# CPU_IO.net
KiCad netlist of a schematic drawn in Altium Designer
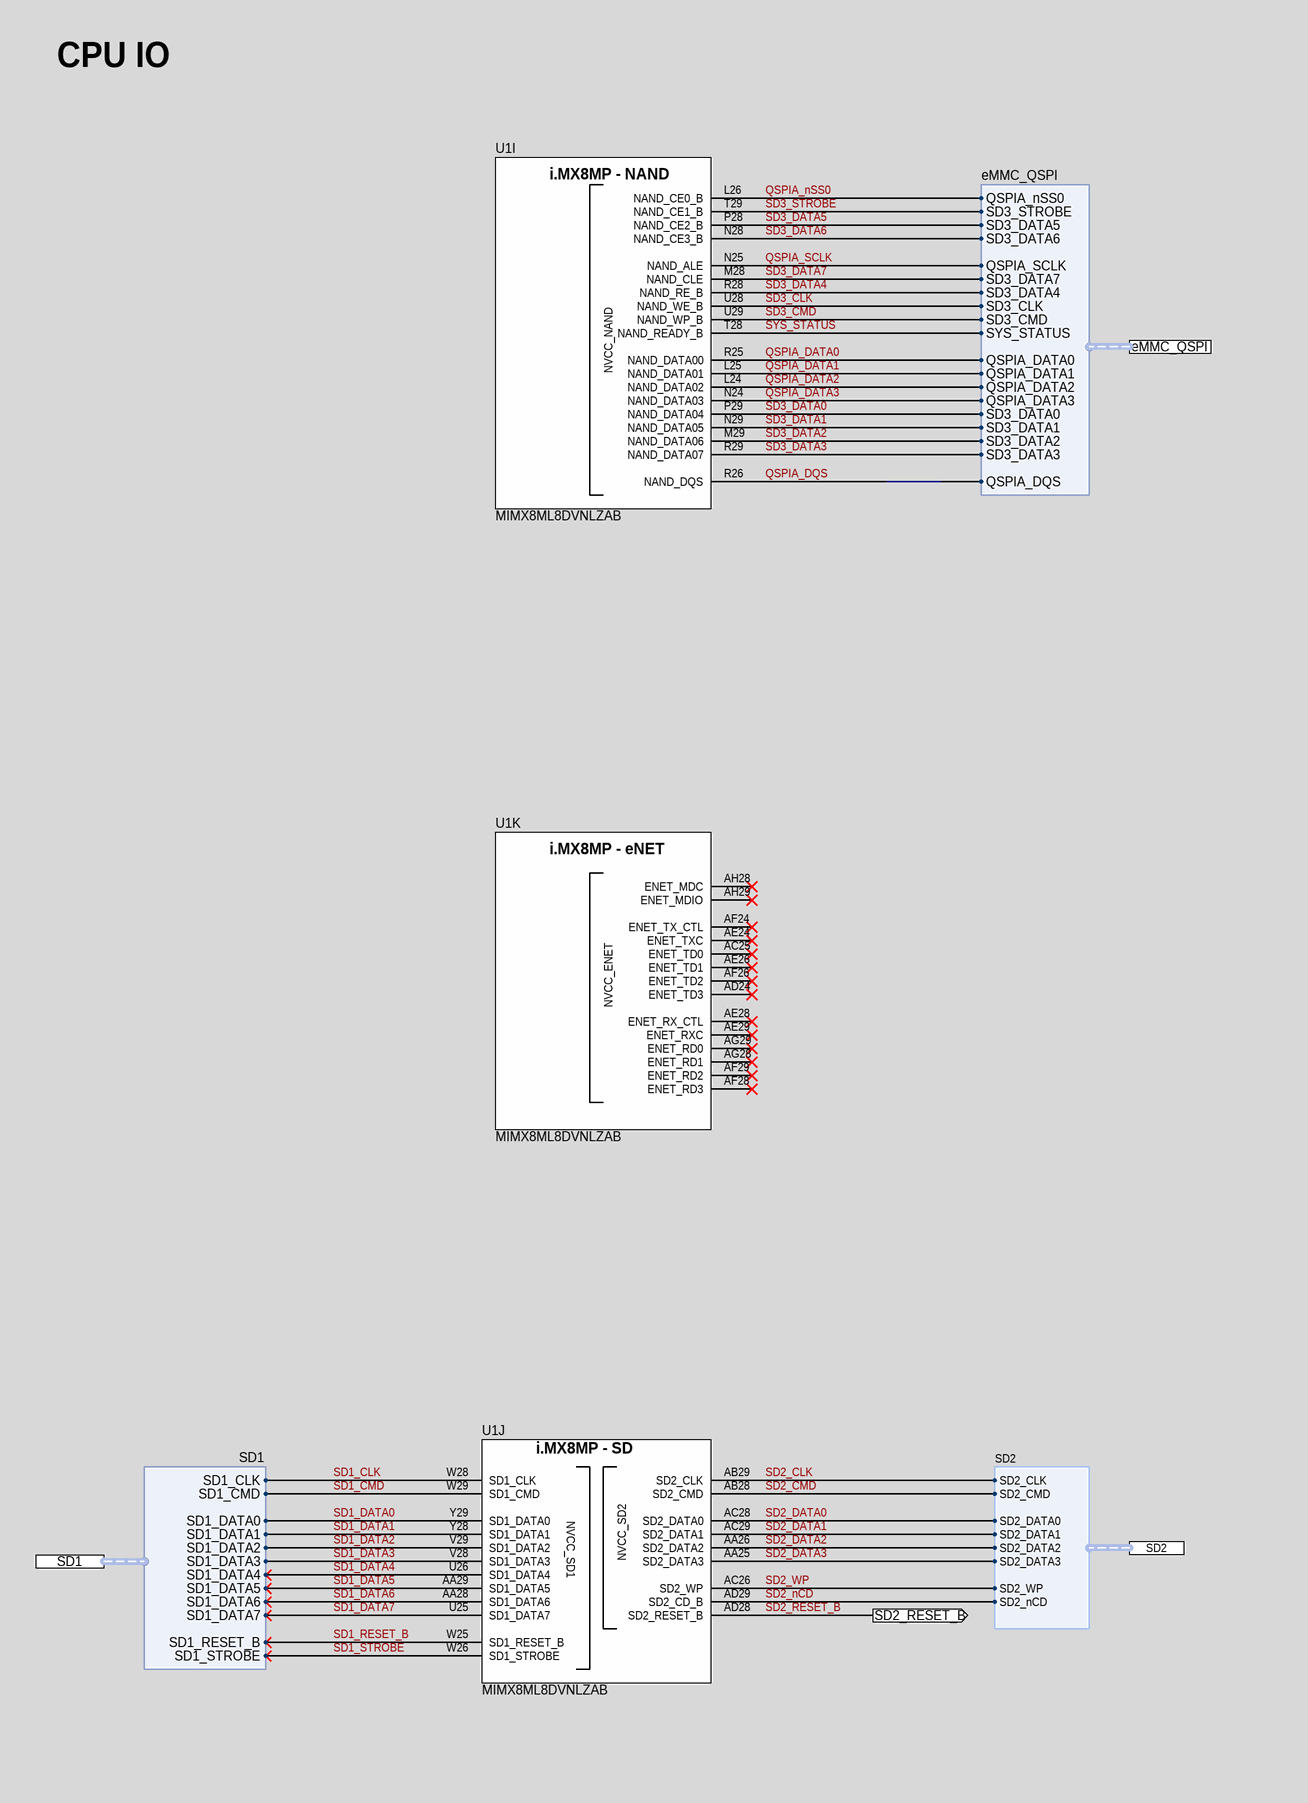
[diagram p0: CPU IO.SchDoc, left]
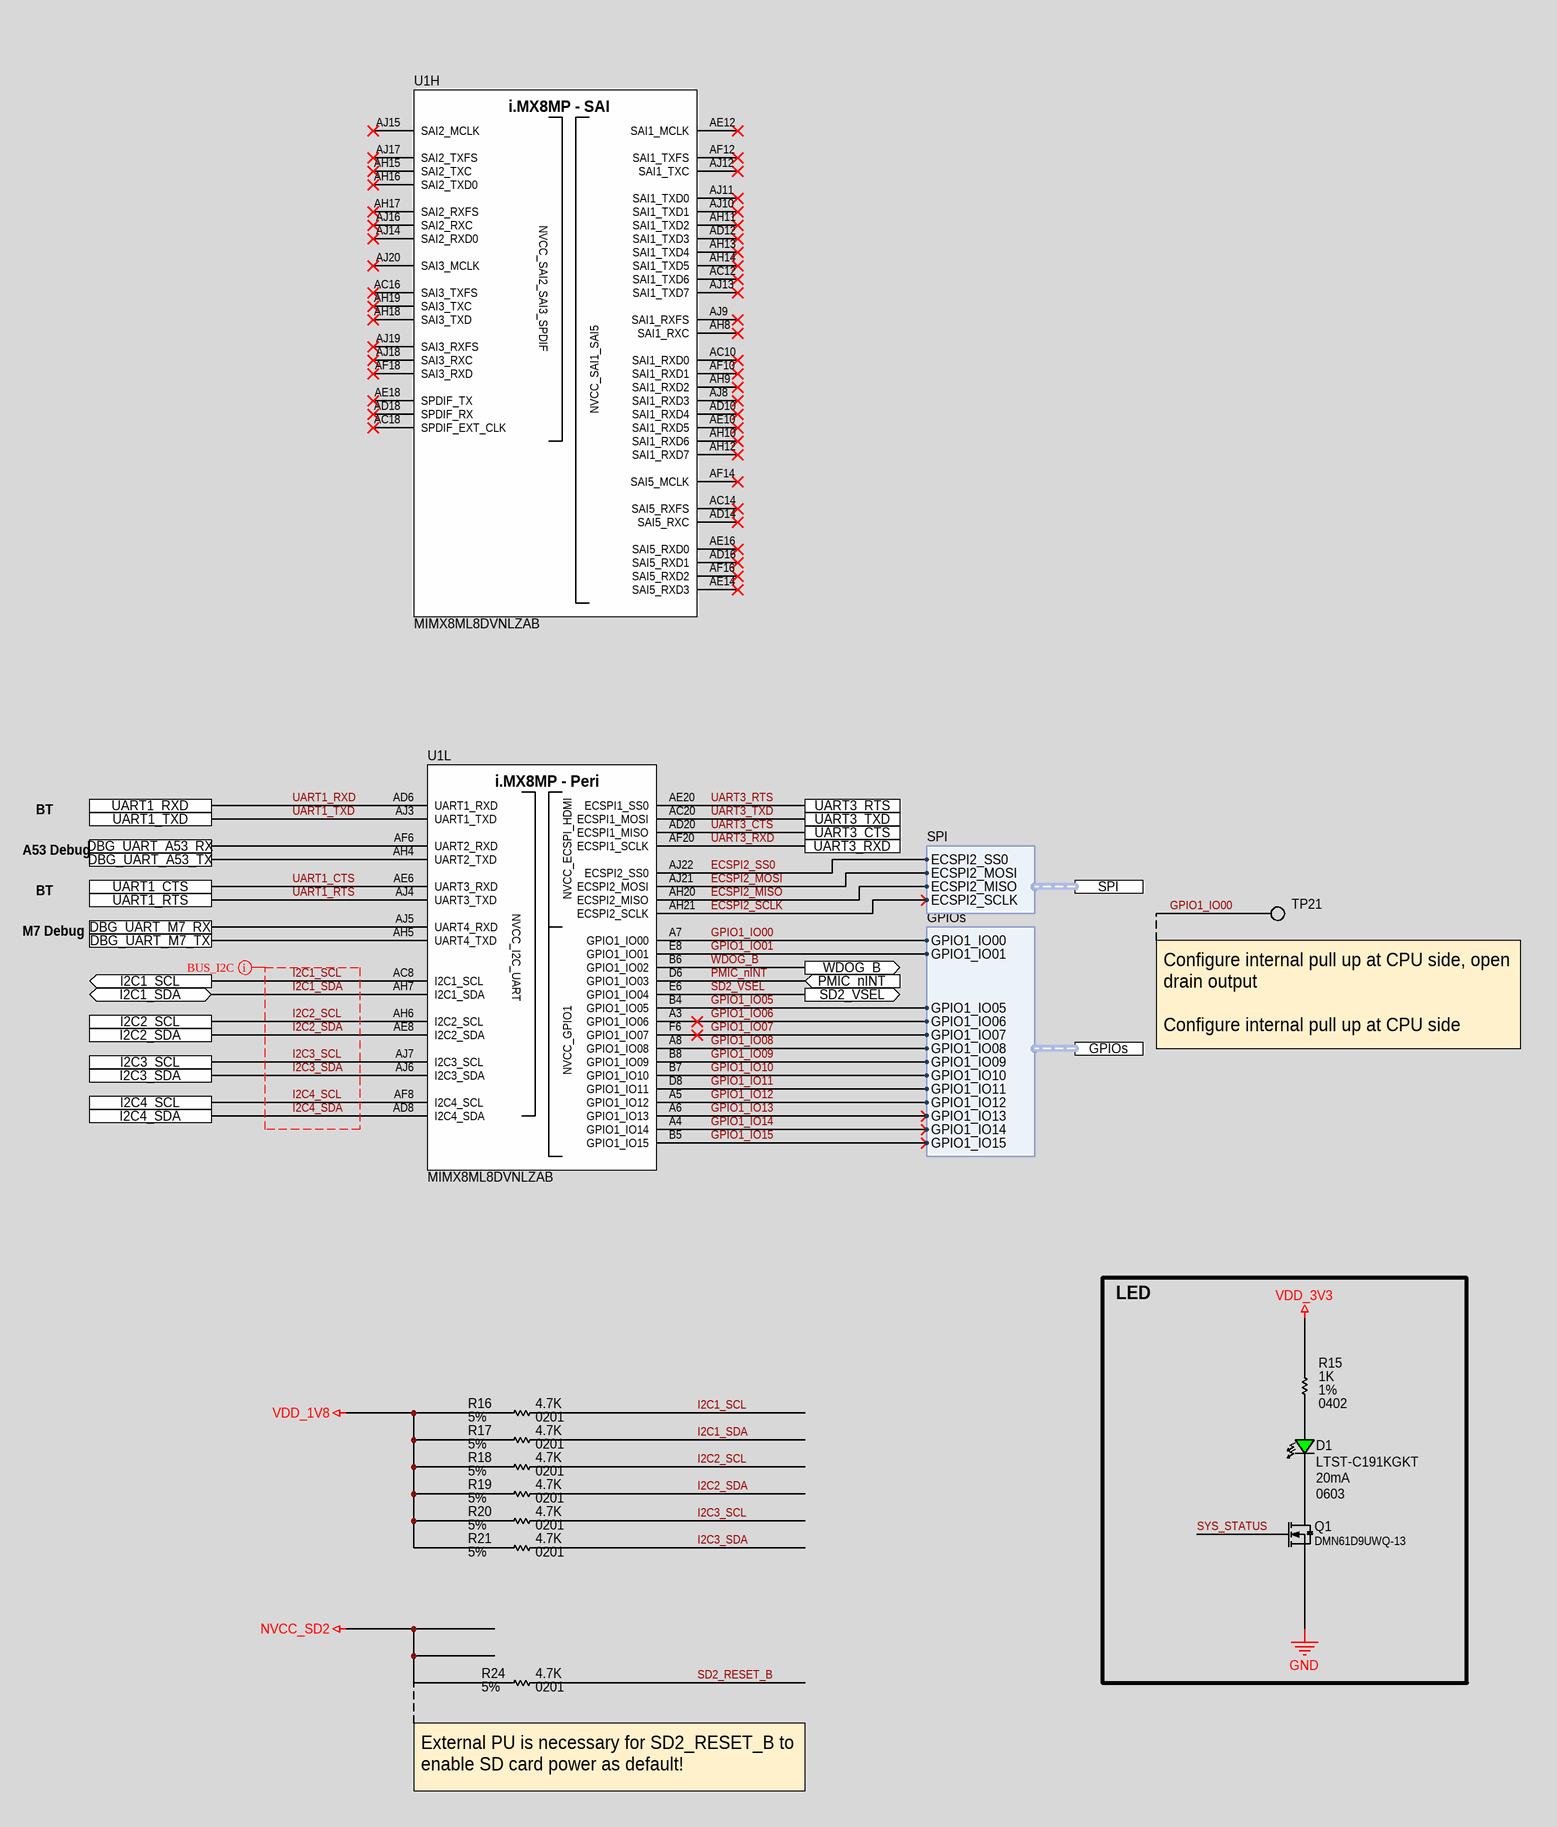
[diagram p1: CPU IO.SchDoc, right]

(export (version "E")
  (design (tool "Eeschema 10.0.6"))
  (components
    (comp (ref "D1")
      (value "LTST-C191KGKT")
      (footprint "LED_0603-GREEN")
      (description "LTST-C191KGKT Lite-On LED, green, 18-71mcd, 130, 1.9V-2.4V SMD, 0603 1.6x0.8x0.55mm RoHS")
      (fields
        (field (name "MANUFACTURER") "Vishay Lite-On")
        (field (name "TEST CURRENT") "20mA")
        (field (name "CASE/PACKAGE") "0603")
      )
      (libsource (lib "Electronic Devices_LIB") (part "LED_DIO_GREEN_20mA_0603"))
    )
    (comp (ref "Q1")
      (value "DMN61D9UWQ-13")
      (footprint "SOT-323")
      (description "N-Channel Enhancement Mode MOSFET 60V 340mA 3-Pin SOT-323 T/R")
      (fields (field (name "MANUFACTURER") "Diodes"))
      (libsource (lib "Electronic Devices_LIB") (part "TRANS_FET_CHA_N_60V_340mA"))
    )
    (comp (ref "R15")
      (value "ERJ-2RKF1001X")
      (footprint "RES_0402_RESC1005X04N")
      (description "RES SMD 1K OHM 1% 1/10W 0402")
      (fields
        (field (name "MANUFACTURER") "Panasonic")
        (field (name "RESISTANCE") "1K")
        (field (name "TOLERANCE") "1%")
        (field (name "CASE/PACKAGE") "0402")
      )
      (libsource (lib "Electronic Devices_LIB") (part "RES_1K_1%_100mW_0402"))
    )
    (comp (ref "R16")
      (value "RK73B1HTTC472J")
      (footprint "RES_0201_RESC0603X02N")
      (description "Res Thick Film 0201 4.7K Ohm 5% 0.05W(1/20W) ±200ppm/C Pad SMD Automotive T/R")
      (fields
        (field (name "MANUFACTURER") "KOA Speer")
        (field (name "TOLERANCE") "5%")
        (field (name "RESISTANCE") "4.7K")
        (field (name "CASE/PACKAGE") "0201")
      )
      (libsource (lib "Electronic Devices_LIB") (part "RES_4.7K_5%_50mW_0201"))
    )
    (comp (ref "R17")
      (value "RK73B1HTTC472J")
      (footprint "RES_0201_RESC0603X02N")
      (description "Res Thick Film 0201 4.7K Ohm 5% 0.05W(1/20W) ±200ppm/C Pad SMD Automotive T/R")
      (fields
        (field (name "MANUFACTURER") "KOA Speer")
        (field (name "TOLERANCE") "5%")
        (field (name "RESISTANCE") "4.7K")
        (field (name "CASE/PACKAGE") "0201")
      )
      (libsource (lib "Electronic Devices_LIB") (part "RES_4.7K_5%_50mW_0201"))
    )
    (comp (ref "R18")
      (value "RK73B1HTTC472J")
      (footprint "RES_0201_RESC0603X02N")
      (description "Res Thick Film 0201 4.7K Ohm 5% 0.05W(1/20W) ±200ppm/C Pad SMD Automotive T/R")
      (fields
        (field (name "MANUFACTURER") "KOA Speer")
        (field (name "TOLERANCE") "5%")
        (field (name "RESISTANCE") "4.7K")
        (field (name "CASE/PACKAGE") "0201")
      )
      (libsource (lib "Electronic Devices_LIB") (part "RES_4.7K_5%_50mW_0201"))
    )
    (comp (ref "R19")
      (value "RK73B1HTTC472J")
      (footprint "RES_0201_RESC0603X02N")
      (description "Res Thick Film 0201 4.7K Ohm 5% 0.05W(1/20W) ±200ppm/C Pad SMD Automotive T/R")
      (fields
        (field (name "MANUFACTURER") "KOA Speer")
        (field (name "TOLERANCE") "5%")
        (field (name "RESISTANCE") "4.7K")
        (field (name "CASE/PACKAGE") "0201")
      )
      (libsource (lib "Electronic Devices_LIB") (part "RES_4.7K_5%_50mW_0201"))
    )
    (comp (ref "R20")
      (value "RK73B1HTTC472J")
      (footprint "RES_0201_RESC0603X02N")
      (description "Res Thick Film 0201 4.7K Ohm 5% 0.05W(1/20W) ±200ppm/C Pad SMD Automotive T/R")
      (fields
        (field (name "MANUFACTURER") "KOA Speer")
        (field (name "TOLERANCE") "5%")
        (field (name "RESISTANCE") "4.7K")
        (field (name "CASE/PACKAGE") "0201")
      )
      (libsource (lib "Electronic Devices_LIB") (part "RES_4.7K_5%_50mW_0201"))
    )
    (comp (ref "R21")
      (value "RK73B1HTTC472J")
      (footprint "RES_0201_RESC0603X02N")
      (description "Res Thick Film 0201 4.7K Ohm 5% 0.05W(1/20W) ±200ppm/C Pad SMD Automotive T/R")
      (fields
        (field (name "MANUFACTURER") "KOA Speer")
        (field (name "TOLERANCE") "5%")
        (field (name "RESISTANCE") "4.7K")
        (field (name "CASE/PACKAGE") "0201")
      )
      (libsource (lib "Electronic Devices_LIB") (part "RES_4.7K_5%_50mW_0201"))
    )
    (comp (ref "R24")
      (value "RK73B1HTTC472J")
      (footprint "RES_0201_RESC0603X02N")
      (description "Res Thick Film 0201 4.7K Ohm 5% 0.05W(1/20W) ±200ppm/C Pad SMD Automotive T/R")
      (fields
        (field (name "MANUFACTURER") "KOA Speer")
        (field (name "TOLERANCE") "5%")
        (field (name "RESISTANCE") "4.7K")
        (field (name "CASE/PACKAGE") "0201")
      )
      (libsource (lib "Electronic Devices_LIB") (part "RES_4.7K_5%_50mW_0201"))
    )
    (comp (ref "TP21")
      (value "NO COMPONENT")
      (footprint "TP_PAD_0.5MM_SMD_ROUND")
      (description "Test Point, SMD pad, round, 1.5mm, 1.6mm, 3mm diameter")
      (libsource (lib "Electronic Devices_LIB") (part "TP_PAD_SMD_SMALL"))
    )
    (comp (ref "U1")
      (value "MIMX8ML8DVNLZAB")
      (footprint "IC_MPU_BGA548C50P29X29_1500X1500X148")
      (description "i.MX 8M Plus, Consumer, / TRAY TRAY MULTIPLE DP BAKEABLE RoHS Compliant: Yes")
      (fields (field (name "MANUFACTURER") "NXP Semiconductors"))
      (libsource (lib "Electronic Devices_LIB") (part "IC_MPU_8M_PLUS_MIMX8ML8DVNLZAB"))
    )
  )
  (nets
    (net (code "6") (name "/DBG_UART_A53_RX") (class "Default")
      (node (ref "U1") (pin "AF6") (pinfunction "UART2_RXD_AF6") (pintype "passive"))
    )
    (net (code "7") (name "/DBG_UART_A53_TX") (class "Default")
      (node (ref "U1") (pin "AH4") (pinfunction "UART2_TXD_AH4") (pintype "passive"))
    )
    (net (code "8") (name "/DBG_UART_M7_RX") (class "Default")
      (node (ref "U1") (pin "AJ5") (pinfunction "UART4_RXD_AJ5") (pintype "passive"))
    )
    (net (code "9") (name "/DBG_UART_M7_TX") (class "Default")
      (node (ref "U1") (pin "AH5") (pinfunction "UART4_TXD_AH5") (pintype "passive"))
    )
    (net (code "10") (name "/ECSPI2_MISO") (class "Default")
      (node (ref "U1") (pin "AH20") (pinfunction "ECSPI2_MISO_AH20") (pintype "passive"))
    )
    (net (code "11") (name "/ECSPI2_MOSI") (class "Default")
      (node (ref "U1") (pin "AJ21") (pinfunction "ECSPI2_MOSI_AJ21") (pintype "passive"))
    )
    (net (code "12") (name "/ECSPI2_SCLK") (class "Default")
      (node (ref "U1") (pin "AH21") (pinfunction "ECSPI2_SCLK_AH21") (pintype "passive+no_connect"))
    )
    (net (code "13") (name "/ECSPI2_SS0") (class "Default")
      (node (ref "U1") (pin "AJ22") (pinfunction "ECSPI2_SS0_AJ22") (pintype "passive"))
    )
    (net (code "14") (name "/GPIO1_IO00") (class "Default")
      (node (ref "TP21") (pin "1") (pinfunction "1_1") (pintype "passive"))
      (node (ref "U1") (pin "A7") (pinfunction "GPIO1_IO00_A7") (pintype "passive"))
    )
    (net (code "15") (name "/GPIO1_IO01") (class "Default")
      (node (ref "U1") (pin "E8") (pinfunction "GPIO1_IO01_E8") (pintype "passive"))
    )
    (net (code "16") (name "/GPIO1_IO05") (class "Default")
      (node (ref "U1") (pin "B4") (pinfunction "GPIO1_IO05_B4") (pintype "passive"))
    )
    (net (code "17") (name "/GPIO1_IO06") (class "Default")
      (node (ref "U1") (pin "A3") (pinfunction "GPIO1_IO06_A3") (pintype "passive+no_connect"))
    )
    (net (code "18") (name "/GPIO1_IO07") (class "Default")
      (node (ref "U1") (pin "F6") (pinfunction "GPIO1_IO07_F6") (pintype "passive+no_connect"))
    )
    (net (code "19") (name "/GPIO1_IO08") (class "Default")
      (node (ref "U1") (pin "A8") (pinfunction "GPIO1_IO08_A8") (pintype "passive"))
    )
    (net (code "20") (name "/GPIO1_IO09") (class "Default")
      (node (ref "U1") (pin "B8") (pinfunction "GPIO1_IO09_B8") (pintype "passive"))
    )
    (net (code "21") (name "/GPIO1_IO10") (class "Default")
      (node (ref "U1") (pin "B7") (pinfunction "GPIO1_IO10_B7") (pintype "passive"))
    )
    (net (code "22") (name "/GPIO1_IO11") (class "Default")
      (node (ref "U1") (pin "D8") (pinfunction "GPIO1_IO11_D8") (pintype "passive"))
    )
    (net (code "23") (name "/GPIO1_IO12") (class "Default")
      (node (ref "U1") (pin "A5") (pinfunction "GPIO1_IO12_A5") (pintype "passive"))
    )
    (net (code "24") (name "/GPIO1_IO13") (class "Default")
      (node (ref "U1") (pin "A6") (pinfunction "GPIO1_IO13_A6") (pintype "passive+no_connect"))
    )
    (net (code "25") (name "/GPIO1_IO14") (class "Default")
      (node (ref "U1") (pin "A4") (pinfunction "GPIO1_IO14_A4") (pintype "passive+no_connect"))
    )
    (net (code "26") (name "/GPIO1_IO15") (class "Default")
      (node (ref "U1") (pin "B5") (pinfunction "GPIO1_IO15_B5") (pintype "passive+no_connect"))
    )
    (net (code "27") (name "/I2C1_SCL") (class "Default")
      (node (ref "R16") (pin "2") (pinfunction "2_2") (pintype "passive"))
      (node (ref "U1") (pin "AC8") (pinfunction "I2C1_SCL_AC8") (pintype "passive"))
    )
    (net (code "28") (name "/I2C1_SDA") (class "Default")
      (node (ref "R17") (pin "2") (pinfunction "2_2") (pintype "passive"))
      (node (ref "U1") (pin "AH7") (pinfunction "I2C1_SDA_AH7") (pintype "passive"))
    )
    (net (code "29") (name "/I2C2_SCL") (class "Default")
      (node (ref "R18") (pin "2") (pinfunction "2_2") (pintype "passive"))
      (node (ref "U1") (pin "AH6") (pinfunction "I2C2_SCL_AH6") (pintype "passive"))
    )
    (net (code "30") (name "/I2C2_SDA") (class "Default")
      (node (ref "R19") (pin "2") (pinfunction "2_2") (pintype "passive"))
      (node (ref "U1") (pin "AE8") (pinfunction "I2C2_SDA_AE8") (pintype "passive"))
    )
    (net (code "31") (name "/I2C3_SCL") (class "Default")
      (node (ref "R20") (pin "2") (pinfunction "2_2") (pintype "passive"))
      (node (ref "U1") (pin "AJ7") (pinfunction "I2C3_SCL_AJ7") (pintype "passive"))
    )
    (net (code "32") (name "/I2C3_SDA") (class "Default")
      (node (ref "R21") (pin "2") (pinfunction "2_2") (pintype "passive"))
      (node (ref "U1") (pin "AJ6") (pinfunction "I2C3_SDA_AJ6") (pintype "passive"))
    )
    (net (code "33") (name "/I2C4_SCL") (class "Default")
      (node (ref "U1") (pin "AF8") (pinfunction "I2C4_SCL_AF8") (pintype "passive"))
    )
    (net (code "34") (name "/I2C4_SDA") (class "Default")
      (node (ref "U1") (pin "AD8") (pinfunction "I2C4_SDA_AD8") (pintype "passive"))
    )
    (net (code "35") (name "/PMIC_nINT") (class "Default")
      (node (ref "U1") (pin "D6") (pinfunction "GPIO1_IO03_D6") (pintype "passive"))
    )
    (net (code "36") (name "/QSPIA_DATA0") (class "Default")
      (node (ref "U1") (pin "R25") (pinfunction "NAND_DATA00_R25") (pintype "passive"))
    )
    (net (code "37") (name "/QSPIA_DATA1") (class "Default")
      (node (ref "U1") (pin "L25") (pinfunction "NAND_DATA01_L25") (pintype "passive"))
    )
    (net (code "38") (name "/QSPIA_DATA2") (class "Default")
      (node (ref "U1") (pin "L24") (pinfunction "NAND_DATA02_L24") (pintype "passive"))
    )
    (net (code "39") (name "/QSPIA_DATA3") (class "Default")
      (node (ref "U1") (pin "N24") (pinfunction "NAND_DATA03_N24") (pintype "passive"))
    )
    (net (code "40") (name "/QSPIA_DQS") (class "Default")
      (node (ref "U1") (pin "R26") (pinfunction "NAND_DQS_R26") (pintype "passive"))
    )
    (net (code "41") (name "/QSPIA_SCLK") (class "Default")
      (node (ref "U1") (pin "N25") (pinfunction "NAND_ALE_N25") (pintype "passive"))
    )
    (net (code "42") (name "/QSPIA_nSS0") (class "Default")
      (node (ref "U1") (pin "L26") (pinfunction "NAND_CE0_B_L26") (pintype "passive"))
    )
    (net (code "43") (name "/SD1_CLK") (class "Default")
      (node (ref "U1") (pin "W28") (pinfunction "SD1_CLK_W28") (pintype "passive"))
    )
    (net (code "44") (name "/SD1_CMD") (class "Default")
      (node (ref "U1") (pin "W29") (pinfunction "SD1_CMD_W29") (pintype "passive"))
    )
    (net (code "45") (name "/SD1_DATA0") (class "Default")
      (node (ref "U1") (pin "Y29") (pinfunction "SD1_DATA0_Y29") (pintype "passive"))
    )
    (net (code "46") (name "/SD1_DATA1") (class "Default")
      (node (ref "U1") (pin "Y28") (pinfunction "SD1_DATA1_Y28") (pintype "passive"))
    )
    (net (code "47") (name "/SD1_DATA2") (class "Default")
      (node (ref "U1") (pin "V29") (pinfunction "SD1_DATA2_V29") (pintype "passive"))
    )
    (net (code "48") (name "/SD1_DATA3") (class "Default")
      (node (ref "U1") (pin "V28") (pinfunction "SD1_DATA3_V28") (pintype "passive"))
    )
    (net (code "49") (name "/SD1_DATA4") (class "Default")
      (node (ref "U1") (pin "U26") (pinfunction "SD1_DATA4_U26") (pintype "passive+no_connect"))
    )
    (net (code "50") (name "/SD1_DATA5") (class "Default")
      (node (ref "U1") (pin "AA29") (pinfunction "SD1_DATA5_AA29") (pintype "passive+no_connect"))
    )
    (net (code "51") (name "/SD1_DATA6") (class "Default")
      (node (ref "U1") (pin "AA28") (pinfunction "SD1_DATA6_AA28") (pintype "passive+no_connect"))
    )
    (net (code "52") (name "/SD1_DATA7") (class "Default")
      (node (ref "U1") (pin "U25") (pinfunction "SD1_DATA7_U25") (pintype "passive+no_connect"))
    )
    (net (code "53") (name "/SD1_RESET_B") (class "Default")
      (node (ref "U1") (pin "W25") (pinfunction "SD1_RESET_B_W25") (pintype "passive+no_connect"))
    )
    (net (code "54") (name "/SD1_STROBE") (class "Default")
      (node (ref "U1") (pin "W26") (pinfunction "SD1_STROBE_W26") (pintype "passive+no_connect"))
    )
    (net (code "55") (name "/SD2_CLK") (class "Default")
      (node (ref "U1") (pin "AB29") (pinfunction "SD2_CLK_AB29") (pintype "passive"))
    )
    (net (code "56") (name "/SD2_CMD") (class "Default")
      (node (ref "U1") (pin "AB28") (pinfunction "SD2_CMD_AB28") (pintype "passive"))
    )
    (net (code "57") (name "/SD2_DATA0") (class "Default")
      (node (ref "U1") (pin "AC28") (pinfunction "SD2_DATA0_AC28") (pintype "passive"))
    )
    (net (code "58") (name "/SD2_DATA1") (class "Default")
      (node (ref "U1") (pin "AC29") (pinfunction "SD2_DATA1_AC29") (pintype "passive"))
    )
    (net (code "59") (name "/SD2_DATA2") (class "Default")
      (node (ref "U1") (pin "AA26") (pinfunction "SD2_DATA2_AA26") (pintype "passive"))
    )
    (net (code "60") (name "/SD2_DATA3") (class "Default")
      (node (ref "U1") (pin "AA25") (pinfunction "SD2_DATA3_AA25") (pintype "passive"))
    )
    (net (code "61") (name "/SD2_RESET_B") (class "Default")
      (node (ref "R24") (pin "2") (pinfunction "2_2") (pintype "passive"))
      (node (ref "U1") (pin "AD28") (pinfunction "SD2_RESET_B_AD28") (pintype "passive"))
    )
    (net (code "62") (name "/SD2_VSEL") (class "Default")
      (node (ref "U1") (pin "E6") (pinfunction "GPIO1_IO04_E6") (pintype "passive"))
    )
    (net (code "63") (name "/SD2_WP") (class "Default")
      (node (ref "U1") (pin "AC26") (pinfunction "SD2_WP_AC26") (pintype "passive"))
    )
    (net (code "64") (name "/SD2_nCD") (class "Default")
      (node (ref "U1") (pin "AD29") (pinfunction "SD2_CD_B_AD29") (pintype "passive"))
    )
    (net (code "65") (name "/SD3_CLK") (class "Default")
      (node (ref "U1") (pin "U28") (pinfunction "NAND_WE_B_U28") (pintype "passive"))
    )
    (net (code "66") (name "/SD3_CMD") (class "Default")
      (node (ref "U1") (pin "U29") (pinfunction "NAND_WP_B_U29") (pintype "passive"))
    )
    (net (code "67") (name "/SD3_DATA0") (class "Default")
      (node (ref "U1") (pin "P29") (pinfunction "NAND_DATA04_P29") (pintype "passive"))
    )
    (net (code "68") (name "/SD3_DATA1") (class "Default")
      (node (ref "U1") (pin "N29") (pinfunction "NAND_DATA05_N29") (pintype "passive"))
    )
    (net (code "69") (name "/SD3_DATA2") (class "Default")
      (node (ref "U1") (pin "M29") (pinfunction "NAND_DATA06_M29") (pintype "passive"))
    )
    (net (code "70") (name "/SD3_DATA3") (class "Default")
      (node (ref "U1") (pin "R29") (pinfunction "NAND_DATA07_R29") (pintype "passive"))
    )
    (net (code "71") (name "/SD3_DATA4") (class "Default")
      (node (ref "U1") (pin "R28") (pinfunction "NAND_RE_B_R28") (pintype "passive"))
    )
    (net (code "72") (name "/SD3_DATA5") (class "Default")
      (node (ref "U1") (pin "P28") (pinfunction "NAND_CE2_B_P28") (pintype "passive"))
    )
    (net (code "73") (name "/SD3_DATA6") (class "Default")
      (node (ref "U1") (pin "N28") (pinfunction "NAND_CE3_B_N28") (pintype "passive"))
    )
    (net (code "74") (name "/SD3_DATA7") (class "Default")
      (node (ref "U1") (pin "M28") (pinfunction "NAND_CLE_M28") (pintype "passive"))
    )
    (net (code "75") (name "/SD3_STROBE") (class "Default")
      (node (ref "U1") (pin "T29") (pinfunction "NAND_CE1_B_T29") (pintype "passive"))
    )
    (net (code "76") (name "/SYS_STATUS") (class "Default")
      (node (ref "Q1") (pin "G") (pinfunction "G_G") (pintype "passive"))
      (node (ref "U1") (pin "T28") (pinfunction "NAND_READY_B_T28") (pintype "passive"))
    )
    (net (code "77") (name "/UART1_CTS") (class "Default")
      (node (ref "U1") (pin "AE6") (pinfunction "UART3_RXD_AE6") (pintype "passive"))
    )
    (net (code "78") (name "/UART1_RTS") (class "Default")
      (node (ref "U1") (pin "AJ4") (pinfunction "UART3_TXD_AJ4") (pintype "passive"))
    )
    (net (code "79") (name "/UART1_RXD") (class "Default")
      (node (ref "U1") (pin "AD6") (pinfunction "UART1_RXD_AD6") (pintype "passive"))
    )
    (net (code "80") (name "/UART1_TXD") (class "Default")
      (node (ref "U1") (pin "AJ3") (pinfunction "UART1_TXD_AJ3") (pintype "passive"))
    )
    (net (code "81") (name "/UART3_CTS") (class "Default")
      (node (ref "U1") (pin "AD20") (pinfunction "ECSPI1_MISO_AD20") (pintype "passive"))
    )
    (net (code "82") (name "/UART3_RTS") (class "Default")
      (node (ref "U1") (pin "AE20") (pinfunction "ECSPI1_SS0_AE20") (pintype "passive"))
    )
    (net (code "83") (name "/UART3_RXD") (class "Default")
      (node (ref "U1") (pin "AF20") (pinfunction "ECSPI1_SCLK_AF20") (pintype "passive"))
    )
    (net (code "84") (name "/UART3_TXD") (class "Default")
      (node (ref "U1") (pin "AC20") (pinfunction "ECSPI1_MOSI_AC20") (pintype "passive"))
    )
    (net (code "85") (name "/WDOG_B") (class "Default")
      (node (ref "U1") (pin "B6") (pinfunction "GPIO1_IO02_B6") (pintype "passive"))
    )
    (net (code "91") (name "GND") (class "Default")
      (node (ref "Q1") (pin "S") (pinfunction "S_S") (pintype "passive"))
    )
    (net (code "92") (name "NVCC_SD2") (class "Default")
      (node (ref "R24") (pin "1") (pinfunction "1_1") (pintype "passive"))
    )
    (net (code "93") (name "Net-(D1-A)") (class "Default")
      (node (ref "D1") (pin "2") (pinfunction "A_2") (pintype "passive"))
      (node (ref "R15") (pin "1") (pinfunction "1_1") (pintype "passive"))
    )
    (net (code "94") (name "Net-(D1-C)") (class "Default")
      (node (ref "D1") (pin "1") (pinfunction "C_1") (pintype "passive"))
      (node (ref "Q1") (pin "D") (pinfunction "D_D") (pintype "passive"))
    )
    (net (code "95") (name "VDD_1V8") (class "Default")
      (node (ref "R16") (pin "1") (pinfunction "1_1") (pintype "passive"))
      (node (ref "R17") (pin "1") (pinfunction "1_1") (pintype "passive"))
      (node (ref "R18") (pin "1") (pinfunction "1_1") (pintype "passive"))
      (node (ref "R19") (pin "1") (pinfunction "1_1") (pintype "passive"))
      (node (ref "R20") (pin "1") (pinfunction "1_1") (pintype "passive"))
      (node (ref "R21") (pin "1") (pinfunction "1_1") (pintype "passive"))
    )
    (net (code "96") (name "VDD_3V3") (class "Default")
      (node (ref "R15") (pin "2") (pinfunction "2_2") (pintype "passive"))
    )
    (net (code "97") (name "unconnected-(U1H-SAI1_MCLK-PadAE12)") (class "Default")
      (node (ref "U1") (pin "AE12") (pinfunction "SAI1_MCLK_AE12") (pintype "passive+no_connect"))
    )
    (net (code "98") (name "unconnected-(U1H-SAI1_RXC-PadAH8)") (class "Default")
      (node (ref "U1") (pin "AH8") (pinfunction "SAI1_RXC_AH8") (pintype "passive+no_connect"))
    )
    (net (code "99") (name "unconnected-(U1H-SAI1_RXD0-PadAC10)") (class "Default")
      (node (ref "U1") (pin "AC10") (pinfunction "SAI1_RXD0_AC10") (pintype "passive+no_connect"))
    )
    (net (code "100") (name "unconnected-(U1H-SAI1_RXD1-PadAF10)") (class "Default")
      (node (ref "U1") (pin "AF10") (pinfunction "SAI1_RXD1_AF10") (pintype "passive+no_connect"))
    )
    (net (code "101") (name "unconnected-(U1H-SAI1_RXD2-PadAH9)") (class "Default")
      (node (ref "U1") (pin "AH9") (pinfunction "SAI1_RXD2_AH9") (pintype "passive+no_connect"))
    )
    (net (code "102") (name "unconnected-(U1H-SAI1_RXD3-PadAJ8)") (class "Default")
      (node (ref "U1") (pin "AJ8") (pinfunction "SAI1_RXD3_AJ8") (pintype "passive+no_connect"))
    )
    (net (code "103") (name "unconnected-(U1H-SAI1_RXD4-PadAD10)") (class "Default")
      (node (ref "U1") (pin "AD10") (pinfunction "SAI1_RXD4_AD10") (pintype "passive+no_connect"))
    )
    (net (code "104") (name "unconnected-(U1H-SAI1_RXD5-PadAE10)") (class "Default")
      (node (ref "U1") (pin "AE10") (pinfunction "SAI1_RXD5_AE10") (pintype "passive+no_connect"))
    )
    (net (code "105") (name "unconnected-(U1H-SAI1_RXD6-PadAH10)") (class "Default")
      (node (ref "U1") (pin "AH10") (pinfunction "SAI1_RXD6_AH10") (pintype "passive+no_connect"))
    )
    (net (code "106") (name "unconnected-(U1H-SAI1_RXD7-PadAH12)") (class "Default")
      (node (ref "U1") (pin "AH12") (pinfunction "SAI1_RXD7_AH12") (pintype "passive+no_connect"))
    )
    (net (code "107") (name "unconnected-(U1H-SAI1_RXFS-PadAJ9)") (class "Default")
      (node (ref "U1") (pin "AJ9") (pinfunction "SAI1_RXFS_AJ9") (pintype "passive+no_connect"))
    )
    (net (code "108") (name "unconnected-(U1H-SAI1_TXC-PadAJ12)") (class "Default")
      (node (ref "U1") (pin "AJ12") (pinfunction "SAI1_TXC_AJ12") (pintype "passive+no_connect"))
    )
    (net (code "109") (name "unconnected-(U1H-SAI1_TXD0-PadAJ11)") (class "Default")
      (node (ref "U1") (pin "AJ11") (pinfunction "SAI1_TXD0_AJ11") (pintype "passive+no_connect"))
    )
    (net (code "110") (name "unconnected-(U1H-SAI1_TXD1-PadAJ10)") (class "Default")
      (node (ref "U1") (pin "AJ10") (pinfunction "SAI1_TXD1_AJ10") (pintype "passive+no_connect"))
    )
    (net (code "111") (name "unconnected-(U1H-SAI1_TXD2-PadAH11)") (class "Default")
      (node (ref "U1") (pin "AH11") (pinfunction "SAI1_TXD2_AH11") (pintype "passive+no_connect"))
    )
    (net (code "112") (name "unconnected-(U1H-SAI1_TXD3-PadAD12)") (class "Default")
      (node (ref "U1") (pin "AD12") (pinfunction "SAI1_TXD3_AD12") (pintype "passive+no_connect"))
    )
    (net (code "113") (name "unconnected-(U1H-SAI1_TXD4-PadAH13)") (class "Default")
      (node (ref "U1") (pin "AH13") (pinfunction "SAI1_TXD4_AH13") (pintype "passive+no_connect"))
    )
    (net (code "114") (name "unconnected-(U1H-SAI1_TXD5-PadAH14)") (class "Default")
      (node (ref "U1") (pin "AH14") (pinfunction "SAI1_TXD5_AH14") (pintype "passive+no_connect"))
    )
    (net (code "115") (name "unconnected-(U1H-SAI1_TXD6-PadAC12)") (class "Default")
      (node (ref "U1") (pin "AC12") (pinfunction "SAI1_TXD6_AC12") (pintype "passive+no_connect"))
    )
    (net (code "116") (name "unconnected-(U1H-SAI1_TXD7-PadAJ13)") (class "Default")
      (node (ref "U1") (pin "AJ13") (pinfunction "SAI1_TXD7_AJ13") (pintype "passive+no_connect"))
    )
    (net (code "117") (name "unconnected-(U1H-SAI1_TXFS-PadAF12)") (class "Default")
      (node (ref "U1") (pin "AF12") (pinfunction "SAI1_TXFS_AF12") (pintype "passive+no_connect"))
    )
    (net (code "118") (name "unconnected-(U1H-SAI2_MCLK-PadAJ15)") (class "Default")
      (node (ref "U1") (pin "AJ15") (pinfunction "SAI2_MCLK_AJ15") (pintype "passive+no_connect"))
    )
    (net (code "119") (name "unconnected-(U1H-SAI2_RXC-PadAJ16)") (class "Default")
      (node (ref "U1") (pin "AJ16") (pinfunction "SAI2_RXC_AJ16") (pintype "passive+no_connect"))
    )
    (net (code "120") (name "unconnected-(U1H-SAI2_RXD0-PadAJ14)") (class "Default")
      (node (ref "U1") (pin "AJ14") (pinfunction "SAI2_RXD0_AJ14") (pintype "passive+no_connect"))
    )
    (net (code "121") (name "unconnected-(U1H-SAI2_RXFS-PadAH17)") (class "Default")
      (node (ref "U1") (pin "AH17") (pinfunction "SAI2_RXFS_AH17") (pintype "passive+no_connect"))
    )
    (net (code "122") (name "unconnected-(U1H-SAI2_TXC-PadAH15)") (class "Default")
      (node (ref "U1") (pin "AH15") (pinfunction "SAI2_TXC_AH15") (pintype "passive+no_connect"))
    )
    (net (code "123") (name "unconnected-(U1H-SAI2_TXD0-PadAH16)") (class "Default")
      (node (ref "U1") (pin "AH16") (pinfunction "SAI2_TXD0_AH16") (pintype "passive+no_connect"))
    )
    (net (code "124") (name "unconnected-(U1H-SAI2_TXFS-PadAJ17)") (class "Default")
      (node (ref "U1") (pin "AJ17") (pinfunction "SAI2_TXFS_AJ17") (pintype "passive+no_connect"))
    )
    (net (code "125") (name "unconnected-(U1H-SAI3_MCLK-PadAJ20)") (class "Default")
      (node (ref "U1") (pin "AJ20") (pinfunction "SAI3_MCLK_AJ20") (pintype "passive+no_connect"))
    )
    (net (code "126") (name "unconnected-(U1H-SAI3_RXC-PadAJ18)") (class "Default")
      (node (ref "U1") (pin "AJ18") (pinfunction "SAI3_RXC_AJ18") (pintype "passive+no_connect"))
    )
    (net (code "127") (name "unconnected-(U1H-SAI3_RXD-PadAF18)") (class "Default")
      (node (ref "U1") (pin "AF18") (pinfunction "SAI3_RXD_AF18") (pintype "passive+no_connect"))
    )
    (net (code "128") (name "unconnected-(U1H-SAI3_RXFS-PadAJ19)") (class "Default")
      (node (ref "U1") (pin "AJ19") (pinfunction "SAI3_RXFS_AJ19") (pintype "passive+no_connect"))
    )
    (net (code "129") (name "unconnected-(U1H-SAI3_TXC-PadAH19)") (class "Default")
      (node (ref "U1") (pin "AH19") (pinfunction "SAI3_TXC_AH19") (pintype "passive+no_connect"))
    )
    (net (code "130") (name "unconnected-(U1H-SAI3_TXD-PadAH18)") (class "Default")
      (node (ref "U1") (pin "AH18") (pinfunction "SAI3_TXD_AH18") (pintype "passive+no_connect"))
    )
    (net (code "131") (name "unconnected-(U1H-SAI3_TXFS-PadAC16)") (class "Default")
      (node (ref "U1") (pin "AC16") (pinfunction "SAI3_TXFS_AC16") (pintype "passive+no_connect"))
    )
    (net (code "132") (name "unconnected-(U1H-SAI5_MCLK-PadAF14)") (class "Default")
      (node (ref "U1") (pin "AF14") (pinfunction "SAI5_MCLK_AF14") (pintype "passive+no_connect"))
    )
    (net (code "133") (name "unconnected-(U1H-SAI5_RXC-PadAD14)") (class "Default")
      (node (ref "U1") (pin "AD14") (pinfunction "SAI5_RXC_AD14") (pintype "passive+no_connect"))
    )
    (net (code "134") (name "unconnected-(U1H-SAI5_RXD0-PadAE16)") (class "Default")
      (node (ref "U1") (pin "AE16") (pinfunction "SAI5_RXD0_AE16") (pintype "passive+no_connect"))
    )
    (net (code "135") (name "unconnected-(U1H-SAI5_RXD1-PadAD16)") (class "Default")
      (node (ref "U1") (pin "AD16") (pinfunction "SAI5_RXD1_AD16") (pintype "passive+no_connect"))
    )
    (net (code "136") (name "unconnected-(U1H-SAI5_RXD2-PadAF16)") (class "Default")
      (node (ref "U1") (pin "AF16") (pinfunction "SAI5_RXD2_AF16") (pintype "passive+no_connect"))
    )
    (net (code "137") (name "unconnected-(U1H-SAI5_RXD3-PadAE14)") (class "Default")
      (node (ref "U1") (pin "AE14") (pinfunction "SAI5_RXD3_AE14") (pintype "passive+no_connect"))
    )
    (net (code "138") (name "unconnected-(U1H-SAI5_RXFS-PadAC14)") (class "Default")
      (node (ref "U1") (pin "AC14") (pinfunction "SAI5_RXFS_AC14") (pintype "passive+no_connect"))
    )
    (net (code "139") (name "unconnected-(U1H-SPDIF_EXT_CLK-PadAC18)") (class "Default")
      (node (ref "U1") (pin "AC18") (pinfunction "SPDIF_EXT_CLK_AC18") (pintype "passive+no_connect"))
    )
    (net (code "140") (name "unconnected-(U1H-SPDIF_RX-PadAD18)") (class "Default")
      (node (ref "U1") (pin "AD18") (pinfunction "SPDIF_RX_AD18") (pintype "passive+no_connect"))
    )
    (net (code "141") (name "unconnected-(U1H-SPDIF_TX-PadAE18)") (class "Default")
      (node (ref "U1") (pin "AE18") (pinfunction "SPDIF_TX_AE18") (pintype "passive+no_connect"))
    )
    (net (code "142") (name "unconnected-(U1K-ENET_MDC-PadAH28)") (class "Default")
      (node (ref "U1") (pin "AH28") (pinfunction "ENET_MDC_AH28") (pintype "passive+no_connect"))
    )
    (net (code "143") (name "unconnected-(U1K-ENET_MDIO-PadAH29)") (class "Default")
      (node (ref "U1") (pin "AH29") (pinfunction "ENET_MDIO_AH29") (pintype "passive+no_connect"))
    )
    (net (code "144") (name "unconnected-(U1K-ENET_RD0-PadAG29)") (class "Default")
      (node (ref "U1") (pin "AG29") (pinfunction "ENET_RD0_AG29") (pintype "passive+no_connect"))
    )
    (net (code "145") (name "unconnected-(U1K-ENET_RD1-PadAG28)") (class "Default")
      (node (ref "U1") (pin "AG28") (pinfunction "ENET_RD1_AG28") (pintype "passive+no_connect"))
    )
    (net (code "146") (name "unconnected-(U1K-ENET_RD2-PadAF29)") (class "Default")
      (node (ref "U1") (pin "AF29") (pinfunction "ENET_RD2_AF29") (pintype "passive+no_connect"))
    )
    (net (code "147") (name "unconnected-(U1K-ENET_RD3-PadAF28)") (class "Default")
      (node (ref "U1") (pin "AF28") (pinfunction "ENET_RD3_AF28") (pintype "passive+no_connect"))
    )
    (net (code "148") (name "unconnected-(U1K-ENET_RXC-PadAE29)") (class "Default")
      (node (ref "U1") (pin "AE29") (pinfunction "ENET_RXC_AE29") (pintype "passive+no_connect"))
    )
    (net (code "149") (name "unconnected-(U1K-ENET_RX_CTL-PadAE28)") (class "Default")
      (node (ref "U1") (pin "AE28") (pinfunction "ENET_RX_CTL_AE28") (pintype "passive+no_connect"))
    )
    (net (code "150") (name "unconnected-(U1K-ENET_TD0-PadAC25)") (class "Default")
      (node (ref "U1") (pin "AC25") (pinfunction "ENET_TD0_AC25") (pintype "passive+no_connect"))
    )
    (net (code "151") (name "unconnected-(U1K-ENET_TD1-PadAE26)") (class "Default")
      (node (ref "U1") (pin "AE26") (pinfunction "ENET_TD1_AE26") (pintype "passive+no_connect"))
    )
    (net (code "152") (name "unconnected-(U1K-ENET_TD2-PadAF26)") (class "Default")
      (node (ref "U1") (pin "AF26") (pinfunction "ENET_TD2_AF26") (pintype "passive+no_connect"))
    )
    (net (code "153") (name "unconnected-(U1K-ENET_TD3-PadAD24)") (class "Default")
      (node (ref "U1") (pin "AD24") (pinfunction "ENET_TD3_AD24") (pintype "passive+no_connect"))
    )
    (net (code "154") (name "unconnected-(U1K-ENET_TXC-PadAE24)") (class "Default")
      (node (ref "U1") (pin "AE24") (pinfunction "ENET_TXC_AE24") (pintype "passive+no_connect"))
    )
    (net (code "155") (name "unconnected-(U1K-ENET_TX_CTL-PadAF24)") (class "Default")
      (node (ref "U1") (pin "AF24") (pinfunction "ENET_TX_CTL_AF24") (pintype "passive+no_connect"))
    )
  )
)
